# 8_USB.net
KiCad netlist of a schematic drawn in Altium Designer
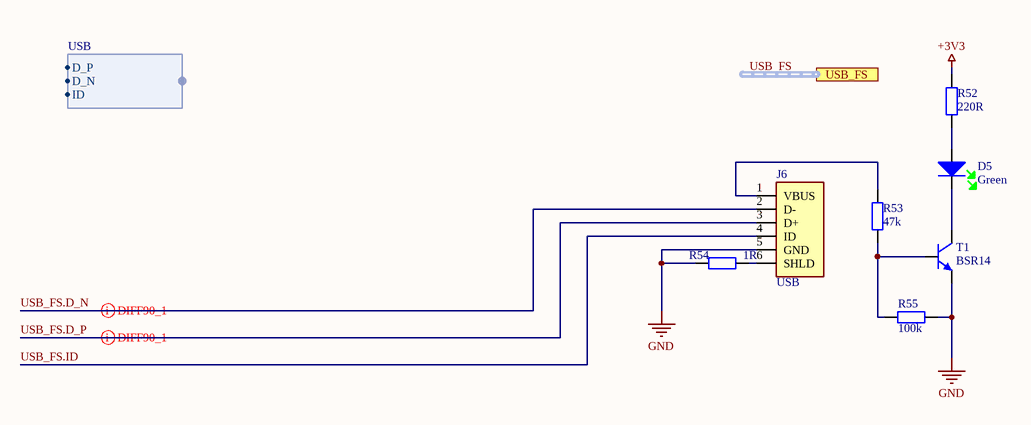
[diagram p0: [8] USB.SchDoc]

(export (version "E")
  (design (tool "Eeschema 10.0.6"))
  (components
    (comp (ref "D5")
      (value "Green")
      (footprint "STguitar:LED 0805 Green")
      (description "Standard LEDs - SMD 0805 Dome Lens LED Green- 570nm")
      (fields
        (field (name "MANUFACTURER PART NUMBER") "APTD2012LCGCK")
        (field (name "MANUFACTURER") "Kingbright")
      )
      (libsource (lib "STguitar") (part "Diode Standard LEDs - SMD 0805 Dome Lens LED Green- 570nm APTD2012LCGCK"))
    )
    (comp (ref "J6")
      (value "USB")
      (footprint "STguitar:Mechanical microUSB 47590-0001")
      (description "USB Connectors MICRO USB AB RECPT RA SMT TOP MNT ASSY")
      (fields (field (name "MANUFACTURER PART NUMBER") "47590-0001") (field (name "MANUFACTURER") "Molex"))
      (libsource (lib "STguitar") (part "Mechanical USB Connectors MICRO USB AB RECPT RA SMT TOP MNT ASSY"))
    )
    (comp (ref "R52")
      (value "220R")
      (footprint "STguitar:Resistor 0603")
      (description "Thin Film Resistors - SMD 1/10W 220 ohm 1% 50ppm")
      (fields
        (field (name "MANUFACTURER PART NUMBER") "RT0603FRE07220RL")
        (field (name "MANUFACTURER") "Yageo")
      )
      (libsource (lib "STguitar") (part "Resistor 220R 1% 0603 RT0603FRE07220RL"))
    )
    (comp (ref "R53")
      (value "47k")
      (footprint "STguitar:Resistor 0603")
      (description "Thin Film Resistors - SMD 1/10W 47K ohm 1% 50ppm")
      (fields
        (field (name "MANUFACTURER PART NUMBER") "RT0603FRE0747KL")
        (field (name "MANUFACTURER") "Yageo")
      )
      (libsource (lib "STguitar") (part "Resistor 47k 1% 0603 RT0603FRE0747KL"))
    )
    (comp (ref "R54")
      (value "1R")
      (footprint "STguitar:Resistor 0603")
      (description "Thin Film Resistors - SMD 1/10W 1 ohm ohm 50 ppm")
      (fields
        (field (name "MANUFACTURER PART NUMBER") "RT0603FRE071RL")
        (field (name "MANUFACTURER") "Yageo")
      )
      (libsource (lib "STguitar") (part "Resistor 1R 1% 0603 RT0603FRE071RL"))
    )
    (comp (ref "R55")
      (value "100k")
      (footprint "STguitar:Resistor 0603")
      (description "Thin Film Resistors - SMD 100K ohm 1% 1/10W")
      (fields
        (field (name "MANUFACTURER PART NUMBER") "RT0603FRE07100KL")
        (field (name "MANUFACTURER") "Yageo")
      )
      (libsource (lib "STguitar") (part "Resistor 100k 1% 0603 RT0603FRE07100KL"))
    )
    (comp (ref "T1")
      (value "BSR14")
      (footprint "STguitar:SOT23-3")
      (description "Bipolar Transistors - BJT NPN Transistor General Purpose")
      (fields (field (name "MANUFACTURER") "ON Semiconductor / Fairchild"))
      (libsource (lib "STguitar") (part "Transistor Bipolar Transistor - BJT NPN Transistor General Purpose"))
    )
  )
  (nets
    (net (code "2") (name "+3V3") (class "Default")
      (node (ref "R52") (pin "2") (pinfunction "2_2") (pintype "passive"))
    )
    (net (code "3") (name "/USB_FS.D_N") (class "Default")
      (node (ref "J6") (pin "2") (pinfunction "D-_2") (pintype "passive"))
    )
    (net (code "4") (name "/USB_FS.D_P") (class "Default")
      (node (ref "J6") (pin "3") (pinfunction "D+_3") (pintype "passive"))
    )
    (net (code "5") (name "/USB_FS.ID") (class "Default")
      (node (ref "J6") (pin "4") (pinfunction "ID_4") (pintype "passive"))
    )
    (net (code "7") (name "GND") (class "Default")
      (node (ref "J6") (pin "5") (pinfunction "GND_5") (pintype "passive"))
      (node (ref "R54") (pin "1") (pinfunction "1_1") (pintype "passive"))
      (node (ref "R55") (pin "2") (pinfunction "2_2") (pintype "passive"))
      (node (ref "T1") (pin "3") (pinfunction "3_3") (pintype "passive"))
    )
    (net (code "8") (name "Net-(D5-Pad1)") (class "Default")
      (node (ref "D5") (pin "1") (pinfunction "1_1") (pintype "passive"))
      (node (ref "T1") (pin "2") (pinfunction "2_2") (pintype "passive"))
    )
    (net (code "9") (name "Net-(D5-Pad2)") (class "Default")
      (node (ref "D5") (pin "2") (pinfunction "2_2") (pintype "passive"))
      (node (ref "R52") (pin "1") (pinfunction "1_1") (pintype "passive"))
    )
    (net (code "10") (name "Net-(J6-SHLD)") (class "Default")
      (node (ref "J6") (pin "6") (pinfunction "SHLD_6") (pintype "passive"))
      (node (ref "R54") (pin "2") (pinfunction "2_2") (pintype "passive"))
    )
    (net (code "11") (name "Net-(J6-VBUS)") (class "Default")
      (node (ref "J6") (pin "1") (pinfunction "VBUS_1") (pintype "passive"))
      (node (ref "R53") (pin "2") (pinfunction "2_2") (pintype "passive"))
    )
    (net (code "12") (name "Net-(R53-Pad1)") (class "Default")
      (node (ref "R53") (pin "1") (pinfunction "1_1") (pintype "passive"))
      (node (ref "R55") (pin "1") (pinfunction "1_1") (pintype "passive"))
      (node (ref "T1") (pin "1") (pinfunction "1_1") (pintype "passive"))
    )
  )
)
